# LED_Controller.net
KiCad netlist of a schematic drawn in Altium Designer
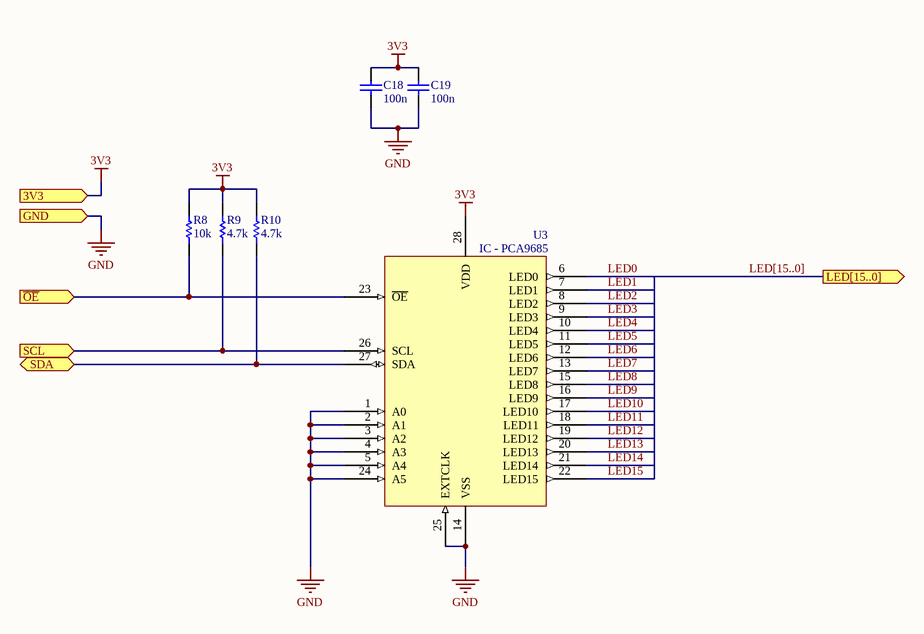
[diagram p0: LED_Controller.SchDoc]

(export (version "E")
  (design (tool "Eeschema 10.0.6"))
  (components
    (comp (ref "C18")
      (value "100n")
      (footprint "CS-0603")
      (fields
        (field (name "TOLERANCE") "10%")
        (field (name "VOLTAGE") "16V")
        (field (name "Comment") "CS - CAPACITOR")
      )
      (libsource (lib "CHINOOK_LIBRARY") (part "CS - CAPACITOR"))
    )
    (comp (ref "C19")
      (value "100n")
      (footprint "CS-0603")
      (fields
        (field (name "TOLERANCE") "10%")
        (field (name "VOLTAGE") "16V")
        (field (name "Comment") "CS - CAPACITOR")
      )
      (libsource (lib "CHINOOK_LIBRARY") (part "CS - CAPACITOR"))
    )
    (comp (ref "R8")
      (value "10k")
      (footprint "RS-0402")
      (fields
        (field (name "TOLERANCE") "RES TOL")
        (field (name "POWER") "RES POWER")
        (field (name "Comment") "RS - RESISTOR")
      )
      (libsource (lib "CHINOOK_LIBRARY") (part "RS - RESISTOR"))
    )
    (comp (ref "R9")
      (value "4.7k")
      (footprint "RS-0402")
      (fields
        (field (name "TOLERANCE") "RES TOL")
        (field (name "POWER") "RES POWER")
        (field (name "Comment") "RS - RESISTOR")
      )
      (libsource (lib "CHINOOK_LIBRARY") (part "RS - RESISTOR"))
    )
    (comp (ref "R10")
      (value "4.7k")
      (footprint "RS-0402")
      (fields
        (field (name "TOLERANCE") "RES TOL")
        (field (name "POWER") "RES POWER")
        (field (name "Comment") "RS - RESISTOR")
      )
      (libsource (lib "CHINOOK_LIBRARY") (part "RS - RESISTOR"))
    )
    (comp (ref "U3")
      (value "IC - PCA9685")
      (footprint "IC-TSSOP-28")
      (description "16-channel, 12-bit PWM Fm + I2C-bus LED controller")
      (fields (field (name "MANUFACTURER") "Allegro"))
      (libsource (lib "CHINOOK_LIBRARY") (part "IC - PCA9685"))
    )
  )
  (nets
    (net (code "1") (name "/LED0") (class "Default")
      (node (ref "U3") (pin "6") (pinfunction "LED0_6") (pintype "output"))
    )
    (net (code "2") (name "/LED1") (class "Default")
      (node (ref "U3") (pin "7") (pinfunction "LED1_7") (pintype "output"))
    )
    (net (code "3") (name "/LED2") (class "Default")
      (node (ref "U3") (pin "8") (pinfunction "LED2_8") (pintype "output"))
    )
    (net (code "4") (name "/LED3") (class "Default")
      (node (ref "U3") (pin "9") (pinfunction "LED3_9") (pintype "output"))
    )
    (net (code "5") (name "/LED4") (class "Default")
      (node (ref "U3") (pin "10") (pinfunction "LED4_10") (pintype "output"))
    )
    (net (code "6") (name "/LED5") (class "Default")
      (node (ref "U3") (pin "11") (pinfunction "LED5_11") (pintype "output"))
    )
    (net (code "7") (name "/LED6") (class "Default")
      (node (ref "U3") (pin "12") (pinfunction "LED6_12") (pintype "output"))
    )
    (net (code "8") (name "/LED7") (class "Default")
      (node (ref "U3") (pin "13") (pinfunction "LED7_13") (pintype "output"))
    )
    (net (code "9") (name "/LED8") (class "Default")
      (node (ref "U3") (pin "15") (pinfunction "LED8_15") (pintype "output"))
    )
    (net (code "10") (name "/LED9") (class "Default")
      (node (ref "U3") (pin "16") (pinfunction "LED9_16") (pintype "output"))
    )
    (net (code "11") (name "/LED10") (class "Default")
      (node (ref "U3") (pin "17") (pinfunction "LED10_17") (pintype "output"))
    )
    (net (code "12") (name "/LED11") (class "Default")
      (node (ref "U3") (pin "18") (pinfunction "LED11_18") (pintype "output"))
    )
    (net (code "13") (name "/LED12") (class "Default")
      (node (ref "U3") (pin "19") (pinfunction "LED12_19") (pintype "output"))
    )
    (net (code "14") (name "/LED13") (class "Default")
      (node (ref "U3") (pin "20") (pinfunction "LED13_20") (pintype "output"))
    )
    (net (code "15") (name "/LED14") (class "Default")
      (node (ref "U3") (pin "21") (pinfunction "LED14_21") (pintype "output"))
    )
    (net (code "16") (name "/LED15") (class "Default")
      (node (ref "U3") (pin "22") (pinfunction "LED15_22") (pintype "output"))
    )
    (net (code "18") (name "/SCL") (class "Default")
      (node (ref "R9") (pin "1") (pinfunction "1_1") (pintype "passive"))
      (node (ref "U3") (pin "26") (pinfunction "SCL_26") (pintype "input"))
    )
    (net (code "19") (name "/SDA") (class "Default")
      (node (ref "R10") (pin "1") (pinfunction "1_1") (pintype "passive"))
      (node (ref "U3") (pin "27") (pinfunction "SDA_27") (pintype "bidirectional"))
    )
    (net (code "20") (name "/~{OE}") (class "Default")
      (node (ref "R8") (pin "1") (pinfunction "1_1") (pintype "passive"))
      (node (ref "U3") (pin "23") (pinfunction "~{OE}_23") (pintype "input"))
    )
    (net (code "21") (name "3V3") (class "Default")
      (node (ref "C18") (pin "1") (pinfunction "1_1") (pintype "passive"))
      (node (ref "C19") (pin "1") (pinfunction "1_1") (pintype "passive"))
      (node (ref "R10") (pin "2") (pinfunction "2_2") (pintype "passive"))
      (node (ref "R8") (pin "2") (pinfunction "2_2") (pintype "passive"))
      (node (ref "R9") (pin "2") (pinfunction "2_2") (pintype "passive"))
      (node (ref "U3") (pin "28") (pinfunction "VDD_28") (pintype "power_in"))
    )
    (net (code "22") (name "GND") (class "Default")
      (node (ref "C18") (pin "2") (pinfunction "2_2") (pintype "passive"))
      (node (ref "C19") (pin "2") (pinfunction "2_2") (pintype "passive"))
      (node (ref "U3") (pin "1") (pinfunction "A0_1") (pintype "input"))
      (node (ref "U3") (pin "14") (pinfunction "VSS_14") (pintype "power_in"))
      (node (ref "U3") (pin "2") (pinfunction "A1_2") (pintype "input"))
      (node (ref "U3") (pin "24") (pinfunction "A5_24") (pintype "input"))
      (node (ref "U3") (pin "25") (pinfunction "EXTCLK_25") (pintype "input"))
      (node (ref "U3") (pin "3") (pinfunction "A2_3") (pintype "input"))
      (node (ref "U3") (pin "4") (pinfunction "A3_4") (pintype "input"))
      (node (ref "U3") (pin "5") (pinfunction "A4_5") (pintype "input"))
    )
  )
)
